# Sheet.net
KiCad netlist of a schematic drawn in Altium Designer
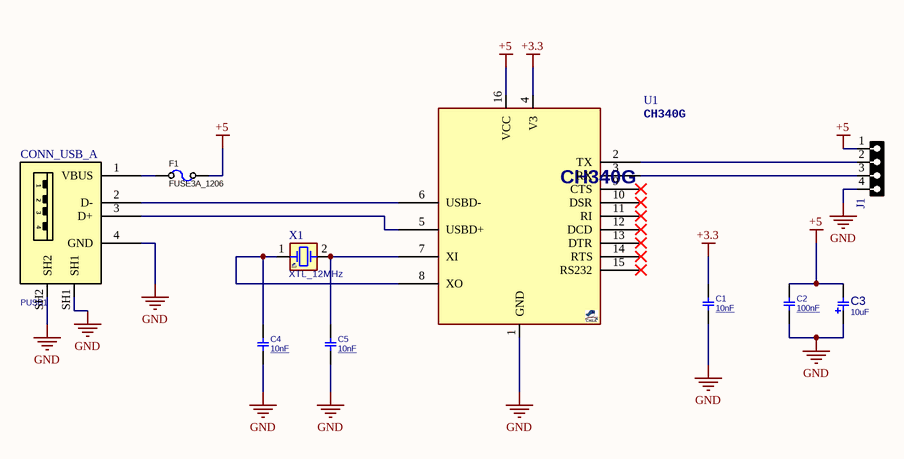
[diagram p0: Sheet.SchDoc]

(export (version "E")
  (design (tool "Eeschema 10.0.6"))
  (components
    (comp (ref "C1")
      (value "10nF")
      (footprint "C1206")
      (description "CAP, FILM, 680nF, 16V, Acryl, 20%, 1206")
      (fields (field (name "MANF") "Murata"))
      (libsource (lib "Chila_PCB") (part "CAP_SMD_FILM"))
    )
    (comp (ref "C2")
      (value "100nF")
      (footprint "C1206")
      (description "CAP, FILM, 680nF, 16V, Acryl, 20%, 1206")
      (fields (field (name "MANF") "Murata"))
      (libsource (lib "Chila_PCB") (part "CAP_SMD_FILM"))
    )
    (comp (ref "C3")
      (value "10uF")
      (footprint "C_EL_5")
      (description "CAP, THD, ELEC,")
      (fields (field (name "MANF_P#") "MANF_PART#") (field (name "MANF") "MANF"))
      (libsource (lib "Chila_PCB") (part "CAP_SMD_EL"))
    )
    (comp (ref "C4")
      (value "10nF")
      (footprint "C1206")
      (description "CAP, FILM, 680nF, 16V, Acryl, 20%, 1206")
      (fields (field (name "MANF") "Murata"))
      (libsource (lib "Chila_PCB") (part "CAP_SMD_FILM"))
    )
    (comp (ref "C5")
      (value "10nF")
      (footprint "C1206")
      (description "CAP, FILM, 680nF, 16V, Acryl, 20%, 1206")
      (fields (field (name "MANF") "Murata"))
      (libsource (lib "Chila_PCB") (part "CAP_SMD_FILM"))
    )
    (comp (ref "F1")
      (value "FUSE3A_1206")
      (footprint "F1206")
      (description "Fuse, 3A, 32VDC, 1206, SMD, Slow Blow")
      (fields (field (name "MANF") "Bourns") (field (name "MANF_P#") "SF-1206SP300-2"))
      (libsource (lib "Chila_PCB") (part "FUSE_3A_1206_SLOW"))
    )
    (comp (ref "J1")
      (value "HDRF4")
      (footprint "HDR_F_1X4")
      (description "CONN, HEADER, Female, pitch: 2.54mm, 4POS")
      (libsource (lib "Chila_PCB") (part "HDR_F_1X4"))
    )
    (comp (ref "PUSB1")
      (value "CONN_USB_A")
      (footprint "USB_A_PLG_RA")
      (description "CONN, USB, A, PLUG, THD")
      (libsource (lib "Chila_PCB") (part "CONN_USB_A_PLUG"))
    )
    (comp (ref "U1")
      (value "CH340G")
      (footprint "SO_16")
      (description "USB-UART")
      (libsource (lib "Chila_PCB") (part "CH340G_SOP16"))
    )
    (comp (ref "X1")
      (value "XTL_12MHz")
      (footprint "XTL_2_11X5")
      (description "Crystal MOST POPULAR ABL HC49 PACKAGE")
      (fields (field (name "MANF") "ABRACON") (field (name "MANF_P#") "ABLS-8.000MHZ-B4-T"))
      (libsource (lib "Chila_PCB") (part "XTL_2_HC49_8MHz_SMD"))
    )
  )
  (nets
    (net (code "1") (name "+3.3") (class "Default")
      (node (ref "C1") (pin "2") (pinfunction "2_2") (pintype "passive"))
      (node (ref "U1") (pin "4") (pinfunction "V3_4") (pintype "passive"))
    )
    (net (code "2") (name "+5") (class "Default")
      (node (ref "C2") (pin "2") (pinfunction "2_2") (pintype "passive"))
      (node (ref "C3") (pin "2") (pinfunction "2_2") (pintype "passive"))
      (node (ref "F1") (pin "2") (pinfunction "2_2") (pintype "passive"))
      (node (ref "J1") (pin "1") (pinfunction "1_1") (pintype "passive"))
      (node (ref "U1") (pin "16") (pinfunction "VCC_16") (pintype "passive"))
    )
    (net (code "3") (name "GND") (class "Default")
      (node (ref "C1") (pin "1") (pinfunction "1_1") (pintype "passive"))
      (node (ref "C2") (pin "1") (pinfunction "1_1") (pintype "passive"))
      (node (ref "C3") (pin "1") (pinfunction "1_1") (pintype "passive"))
      (node (ref "C4") (pin "1") (pinfunction "1_1") (pintype "passive"))
      (node (ref "C5") (pin "1") (pinfunction "1_1") (pintype "passive"))
      (node (ref "J1") (pin "4") (pinfunction "4_4") (pintype "passive"))
      (node (ref "PUSB1") (pin "4") (pinfunction "GND_4") (pintype "passive"))
      (node (ref "PUSB1") (pin "SH1") (pinfunction "SH1_SH1") (pintype "passive"))
      (node (ref "PUSB1") (pin "SH2") (pinfunction "SH2_SH2") (pintype "passive"))
      (node (ref "U1") (pin "1") (pinfunction "GND_1") (pintype "passive"))
    )
    (net (code "4") (name "Net-(PUSB1-D+)") (class "Default")
      (node (ref "PUSB1") (pin "3") (pinfunction "D+_3") (pintype "passive"))
      (node (ref "U1") (pin "5") (pinfunction "USBD+_5") (pintype "passive"))
    )
    (net (code "5") (name "Net-(PUSB1-D-)") (class "Default")
      (node (ref "PUSB1") (pin "2") (pinfunction "D-_2") (pintype "passive"))
      (node (ref "U1") (pin "6") (pinfunction "USBD-_6") (pintype "passive"))
    )
    (net (code "6") (name "Net-(PUSB1-VBUS)") (class "Default")
      (node (ref "F1") (pin "1") (pinfunction "1_1") (pintype "passive"))
      (node (ref "PUSB1") (pin "1") (pinfunction "VBUS_1") (pintype "passive"))
    )
    (net (code "7") (name "Net-(U1-RX)") (class "Default")
      (node (ref "J1") (pin "3") (pinfunction "3_3") (pintype "passive"))
      (node (ref "U1") (pin "3") (pinfunction "RX_3") (pintype "passive"))
    )
    (net (code "8") (name "Net-(U1-TX)") (class "Default")
      (node (ref "J1") (pin "2") (pinfunction "2_2") (pintype "passive"))
      (node (ref "U1") (pin "2") (pinfunction "TX_2") (pintype "passive"))
    )
    (net (code "9") (name "Net-(U1-XI)") (class "Default")
      (node (ref "C5") (pin "2") (pinfunction "2_2") (pintype "passive"))
      (node (ref "U1") (pin "7") (pinfunction "XI_7") (pintype "passive"))
      (node (ref "X1") (pin "2") (pinfunction "OSC2_2") (pintype "passive"))
    )
    (net (code "10") (name "Net-(U1-XO)") (class "Default")
      (node (ref "C4") (pin "2") (pinfunction "2_2") (pintype "passive"))
      (node (ref "U1") (pin "8") (pinfunction "XO_8") (pintype "passive"))
      (node (ref "X1") (pin "1") (pinfunction "OSC1_1") (pintype "passive"))
    )
    (net (code "11") (name "unconnected-(U1-CTS-Pad9)") (class "Default")
      (node (ref "U1") (pin "9") (pinfunction "CTS_9") (pintype "passive+no_connect"))
    )
    (net (code "12") (name "unconnected-(U1-DCD-Pad12)") (class "Default")
      (node (ref "U1") (pin "12") (pinfunction "DCD_12") (pintype "passive+no_connect"))
    )
    (net (code "13") (name "unconnected-(U1-DSR-Pad10)") (class "Default")
      (node (ref "U1") (pin "10") (pinfunction "DSR_10") (pintype "passive+no_connect"))
    )
    (net (code "14") (name "unconnected-(U1-DTR-Pad13)") (class "Default")
      (node (ref "U1") (pin "13") (pinfunction "DTR_13") (pintype "passive+no_connect"))
    )
    (net (code "15") (name "unconnected-(U1-RI-Pad11)") (class "Default")
      (node (ref "U1") (pin "11") (pinfunction "RI_11") (pintype "passive+no_connect"))
    )
    (net (code "16") (name "unconnected-(U1-RS232-Pad15)") (class "Default")
      (node (ref "U1") (pin "15") (pinfunction "RS232_15") (pintype "passive+no_connect"))
    )
    (net (code "17") (name "unconnected-(U1-RTS-Pad14)") (class "Default")
      (node (ref "U1") (pin "14") (pinfunction "RTS_14") (pintype "passive+no_connect"))
    )
  )
)
